# CC2530.net
KiCad netlist of a schematic drawn in Altium Designer
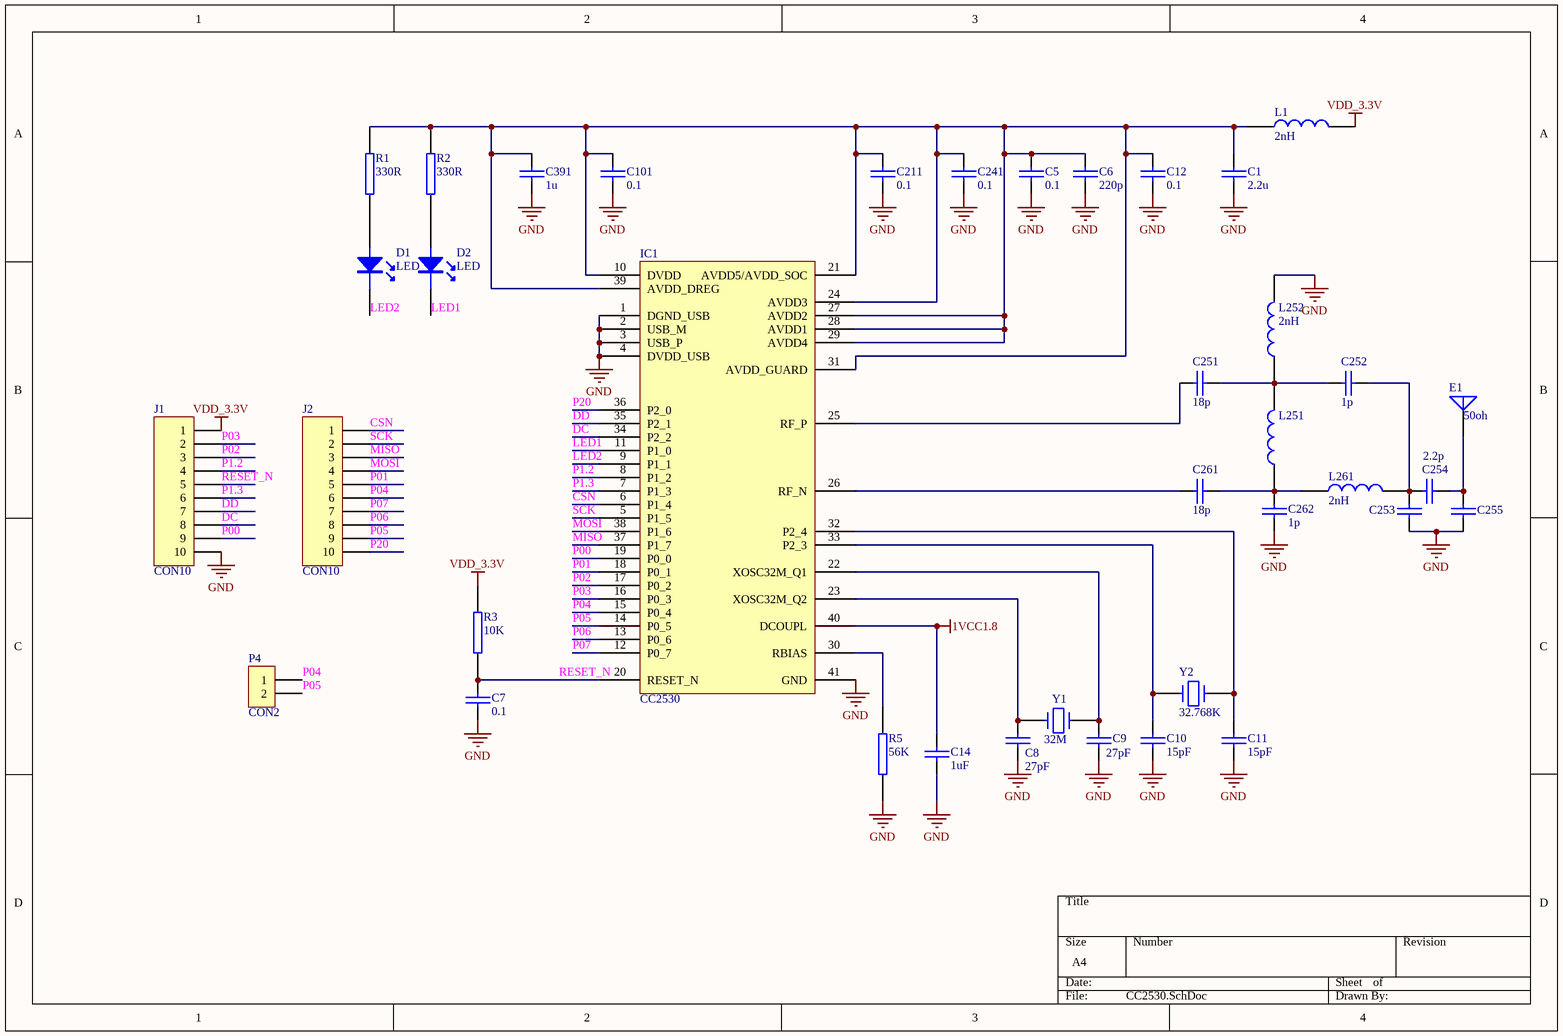
[diagram p0: CC2530.SchDoc]

(export (version "E")
  (design (tool "Eeschema 10.0.6"))
  (components
    (comp (ref "C1")
      (value "2.2u")
      (footprint "0402")
      (description "Capacitor")
      (libsource (lib "Miscellaneous Devices") (part "CAP"))
    )
    (comp (ref "C5")
      (value "0.1")
      (footprint "0402")
      (description "Capacitor")
      (libsource (lib "Miscellaneous Devices") (part "CAP"))
    )
    (comp (ref "C6")
      (value "220p")
      (footprint "0402")
      (description "Capacitor")
      (libsource (lib "Miscellaneous Devices") (part "CAP"))
    )
    (comp (ref "C7")
      (value "0.1")
      (footprint "0402")
      (description "Capacitor")
      (libsource (lib "Miscellaneous Devices") (part "CAP"))
    )
    (comp (ref "C8")
      (value "27pF")
      (footprint "0402")
      (description "Capacitor")
      (libsource (lib "Miscellaneous Devices") (part "CAP"))
    )
    (comp (ref "C9")
      (value "27pF")
      (footprint "0402")
      (description "Capacitor")
      (libsource (lib "Miscellaneous Devices") (part "CAP"))
    )
    (comp (ref "C10")
      (value "15pF")
      (footprint "0402")
      (description "Capacitor")
      (libsource (lib "Miscellaneous Devices") (part "CAP"))
    )
    (comp (ref "C11")
      (value "15pF")
      (footprint "0402")
      (description "Capacitor")
      (libsource (lib "Miscellaneous Devices") (part "CAP"))
    )
    (comp (ref "C12")
      (value "0.1")
      (footprint "0402")
      (description "Capacitor")
      (libsource (lib "Miscellaneous Devices") (part "CAP"))
    )
    (comp (ref "C14")
      (value "1uF")
      (footprint "0402")
      (description "Capacitor")
      (libsource (lib "Miscellaneous Devices") (part "CAP"))
    )
    (comp (ref "C101")
      (value "0.1")
      (footprint "0402")
      (description "Capacitor")
      (libsource (lib "Miscellaneous Devices") (part "CAP"))
    )
    (comp (ref "C211")
      (value "0.1")
      (footprint "0402")
      (description "Capacitor")
      (libsource (lib "Miscellaneous Devices") (part "CAP"))
    )
    (comp (ref "C241")
      (value "0.1")
      (footprint "0402")
      (description "Capacitor")
      (libsource (lib "Miscellaneous Devices") (part "CAP"))
    )
    (comp (ref "C251")
      (value "18p")
      (footprint "0402")
      (description "Capacitor")
      (libsource (lib "Miscellaneous Devices") (part "CAP"))
    )
    (comp (ref "C252")
      (value "1p")
      (footprint "0402")
      (description "Capacitor")
      (libsource (lib "Miscellaneous Devices") (part "CAP"))
    )
    (comp (ref "C253")
      (value "~")
      (footprint "0402")
      (description "Capacitor")
      (libsource (lib "Miscellaneous Devices") (part "CAP"))
    )
    (comp (ref "C254")
      (value "2.2p")
      (footprint "0402")
      (description "Capacitor")
      (libsource (lib "Miscellaneous Devices") (part "CAP"))
    )
    (comp (ref "C255")
      (value "~")
      (footprint "0402")
      (description "Capacitor")
      (libsource (lib "Miscellaneous Devices") (part "CAP"))
    )
    (comp (ref "C261")
      (value "18p")
      (footprint "0402")
      (description "Capacitor")
      (libsource (lib "Miscellaneous Devices") (part "CAP"))
    )
    (comp (ref "C262")
      (value "1p")
      (footprint "0402")
      (description "Capacitor")
      (libsource (lib "Miscellaneous Devices") (part "CAP"))
    )
    (comp (ref "C391")
      (value "1u")
      (footprint "0402")
      (description "Capacitor")
      (libsource (lib "Miscellaneous Devices") (part "CAP"))
    )
    (comp (ref "D1")
      (value "LED")
      (footprint "LED-0603")
      (libsource (lib "Miscellaneous Devices") (part "LED"))
    )
    (comp (ref "D2")
      (value "LED")
      (footprint "LED-0603")
      (libsource (lib "Miscellaneous Devices") (part "LED"))
    )
    (comp (ref "E1")
      (value "50oh")
      (footprint "ANT")
      (description "Generic Antenna")
      (libsource (lib "Miscellaneous Devices") (part "ANTENNA"))
    )
    (comp (ref "IC1") (value "CC2530") (footprint "PVQFN-N40") (libsource (lib "集成") (part "CC2530")))
    (comp (ref "J1")
      (value "CON10")
      (footprint "SIP10-2.0")
      (description "Connector")
      (libsource (lib "Miscellaneous Devices") (part "CON10"))
    )
    (comp (ref "J2")
      (value "CON10")
      (footprint "SIP10-2.0")
      (description "Connector")
      (libsource (lib "Miscellaneous Devices") (part "CON10"))
    )
    (comp (ref "L1")
      (value "2nH")
      (footprint "0402")
      (libsource (lib "Miscellaneous Devices") (part "INDUCTOR"))
    )
    (comp (ref "L251")
      (value "~")
      (footprint "0402")
      (libsource (lib "Miscellaneous Devices") (part "INDUCTOR"))
    )
    (comp (ref "L252")
      (value "2nH")
      (footprint "0402")
      (libsource (lib "Miscellaneous Devices") (part "INDUCTOR"))
    )
    (comp (ref "L261")
      (value "2nH")
      (footprint "0402")
      (libsource (lib "Miscellaneous Devices") (part "INDUCTOR"))
    )
    (comp (ref "P4")
      (value "CON2")
      (footprint "SIP2")
      (description "Connector")
      (libsource (lib "Miscellaneous Devices_99se") (part "CON2"))
    )
    (comp (ref "R1")
      (value "330R")
      (footprint "0402")
      (libsource (lib "Miscellaneous Devices") (part "RES2"))
    )
    (comp (ref "R2")
      (value "330R")
      (footprint "0402")
      (libsource (lib "Miscellaneous Devices") (part "RES2"))
    )
    (comp (ref "R3") (value "10K") (footprint "0402") (libsource (lib "Miscellaneous Devices") (part "RES2")))
    (comp (ref "R5") (value "56K") (footprint "0402") (libsource (lib "Miscellaneous Devices") (part "RES2")))
    (comp (ref "Y1")
      (value "32M")
      (footprint "XT-SMD3225")
      (description "Crystal")
      (libsource (lib "Miscellaneous Devices") (part "CRYSTAL"))
    )
    (comp (ref "Y2")
      (value "32.768K")
      (footprint "XT_3")
      (description "Crystal")
      (libsource (lib "Miscellaneous Devices") (part "CRYSTAL"))
    )
  )
  (nets
    (net (code "1") (name "/CSN") (class "Default")
      (node (ref "IC1") (pin "6") (pinfunction "P1_4_6") (pintype "passive"))
      (node (ref "J2") (pin "1") (pinfunction "1_1") (pintype "passive"))
    )
    (net (code "2") (name "/DC") (class "Default")
      (node (ref "IC1") (pin "34") (pinfunction "P2_2_34") (pintype "passive"))
      (node (ref "J1") (pin "8") (pinfunction "8_8") (pintype "passive"))
    )
    (net (code "3") (name "/DD") (class "Default")
      (node (ref "IC1") (pin "35") (pinfunction "P2_1_35") (pintype "passive"))
      (node (ref "J1") (pin "7") (pinfunction "7_7") (pintype "passive"))
    )
    (net (code "4") (name "/LED1") (class "Default")
      (node (ref "D2") (pin "K") (pinfunction "2_K") (pintype "passive"))
      (node (ref "IC1") (pin "11") (pinfunction "P1_0_11") (pintype "passive"))
    )
    (net (code "5") (name "/LED2") (class "Default")
      (node (ref "D1") (pin "K") (pinfunction "2_K") (pintype "passive"))
      (node (ref "IC1") (pin "9") (pinfunction "P1_1_9") (pintype "passive"))
    )
    (net (code "6") (name "/MISO") (class "Default")
      (node (ref "IC1") (pin "37") (pinfunction "P1_7_37") (pintype "passive"))
      (node (ref "J2") (pin "3") (pinfunction "3_3") (pintype "passive"))
    )
    (net (code "7") (name "/MOSI") (class "Default")
      (node (ref "IC1") (pin "38") (pinfunction "P1_6_38") (pintype "passive"))
      (node (ref "J2") (pin "4") (pinfunction "4_4") (pintype "passive"))
    )
    (net (code "8") (name "/P00") (class "Default")
      (node (ref "IC1") (pin "19") (pinfunction "P0_0_19") (pintype "passive"))
      (node (ref "J1") (pin "9") (pinfunction "9_9") (pintype "passive"))
    )
    (net (code "9") (name "/P01") (class "Default")
      (node (ref "IC1") (pin "18") (pinfunction "P0_1_18") (pintype "passive"))
      (node (ref "J2") (pin "5") (pinfunction "5_5") (pintype "passive"))
    )
    (net (code "10") (name "/P1.2") (class "Default")
      (node (ref "IC1") (pin "8") (pinfunction "P1_2_8") (pintype "passive"))
      (node (ref "J1") (pin "4") (pinfunction "4_4") (pintype "passive"))
    )
    (net (code "11") (name "/P1.3") (class "Default")
      (node (ref "IC1") (pin "7") (pinfunction "P1_3_7") (pintype "passive"))
      (node (ref "J1") (pin "6") (pinfunction "6_6") (pintype "passive"))
    )
    (net (code "12") (name "/P02") (class "Default")
      (node (ref "IC1") (pin "17") (pinfunction "P0_2_17") (pintype "passive"))
      (node (ref "J1") (pin "3") (pinfunction "3_3") (pintype "passive"))
    )
    (net (code "13") (name "/P03") (class "Default")
      (node (ref "IC1") (pin "16") (pinfunction "P0_3_16") (pintype "passive"))
      (node (ref "J1") (pin "2") (pinfunction "2_2") (pintype "passive"))
    )
    (net (code "14") (name "/P04") (class "Default")
      (node (ref "IC1") (pin "15") (pinfunction "P0_4_15") (pintype "passive"))
      (node (ref "J2") (pin "6") (pinfunction "6_6") (pintype "passive"))
      (node (ref "P4") (pin "1") (pinfunction "1_1") (pintype "passive"))
    )
    (net (code "15") (name "/P05") (class "Default")
      (node (ref "IC1") (pin "14") (pinfunction "P0_5_14") (pintype "passive"))
      (node (ref "J2") (pin "9") (pinfunction "9_9") (pintype "passive"))
      (node (ref "P4") (pin "2") (pinfunction "2_2") (pintype "passive"))
    )
    (net (code "16") (name "/P06") (class "Default")
      (node (ref "IC1") (pin "13") (pinfunction "P0_6_13") (pintype "passive"))
      (node (ref "J2") (pin "8") (pinfunction "8_8") (pintype "passive"))
    )
    (net (code "17") (name "/P07") (class "Default")
      (node (ref "IC1") (pin "12") (pinfunction "P0_7_12") (pintype "passive"))
      (node (ref "J2") (pin "7") (pinfunction "7_7") (pintype "passive"))
    )
    (net (code "18") (name "/P20") (class "Default")
      (node (ref "IC1") (pin "36") (pinfunction "P2_0_36") (pintype "passive"))
      (node (ref "J2") (pin "10") (pinfunction "10_10") (pintype "passive"))
    )
    (net (code "19") (name "/RESET_N") (class "Default")
      (node (ref "C7") (pin "1") (pinfunction "1_1") (pintype "passive"))
      (node (ref "IC1") (pin "20") (pinfunction "RESET_N_20") (pintype "passive"))
      (node (ref "J1") (pin "5") (pinfunction "5_5") (pintype "passive"))
      (node (ref "R3") (pin "1") (pinfunction "1_1") (pintype "passive"))
    )
    (net (code "20") (name "/SCK") (class "Default")
      (node (ref "IC1") (pin "5") (pinfunction "P1_5_5") (pintype "passive"))
      (node (ref "J2") (pin "2") (pinfunction "2_2") (pintype "passive"))
    )
    (net (code "21") (name "1VCC1.8") (class "Default")
      (node (ref "C14") (pin "1") (pinfunction "1_1") (pintype "passive"))
      (node (ref "IC1") (pin "40") (pinfunction "DCOUPL_40") (pintype "passive"))
    )
    (net (code "22") (name "GND") (class "Default")
      (node (ref "C1") (pin "2") (pinfunction "2_2") (pintype "passive"))
      (node (ref "C10") (pin "2") (pinfunction "2_2") (pintype "passive"))
      (node (ref "C101") (pin "2") (pinfunction "2_2") (pintype "passive"))
      (node (ref "C11") (pin "2") (pinfunction "2_2") (pintype "passive"))
      (node (ref "C12") (pin "2") (pinfunction "2_2") (pintype "passive"))
      (node (ref "C14") (pin "2") (pinfunction "2_2") (pintype "passive"))
      (node (ref "C211") (pin "2") (pinfunction "2_2") (pintype "passive"))
      (node (ref "C241") (pin "2") (pinfunction "2_2") (pintype "passive"))
      (node (ref "C253") (pin "2") (pinfunction "2_2") (pintype "passive"))
      (node (ref "C255") (pin "1") (pinfunction "1_1") (pintype "passive"))
      (node (ref "C262") (pin "2") (pinfunction "2_2") (pintype "passive"))
      (node (ref "C391") (pin "2") (pinfunction "2_2") (pintype "passive"))
      (node (ref "C5") (pin "2") (pinfunction "2_2") (pintype "passive"))
      (node (ref "C6") (pin "2") (pinfunction "2_2") (pintype "passive"))
      (node (ref "C7") (pin "2") (pinfunction "2_2") (pintype "passive"))
      (node (ref "C8") (pin "2") (pinfunction "2_2") (pintype "passive"))
      (node (ref "C9") (pin "2") (pinfunction "2_2") (pintype "passive"))
      (node (ref "IC1") (pin "1") (pinfunction "DGND_USB_1") (pintype "passive"))
      (node (ref "IC1") (pin "2") (pinfunction "USB_M_2") (pintype "passive"))
      (node (ref "IC1") (pin "3") (pinfunction "USB_P_3") (pintype "passive"))
      (node (ref "IC1") (pin "4") (pinfunction "DVDD_USB_4") (pintype "passive"))
      (node (ref "IC1") (pin "41") (pinfunction "GND_41") (pintype "passive"))
      (node (ref "J1") (pin "10") (pinfunction "10_10") (pintype "passive"))
      (node (ref "L252") (pin "2") (pinfunction "2_2") (pintype "passive"))
      (node (ref "R5") (pin "2") (pinfunction "2_2") (pintype "passive"))
    )
    (net (code "23") (name "Net-(C251-Pad2)") (class "Default")
      (node (ref "C251") (pin "2") (pinfunction "2_2") (pintype "passive"))
      (node (ref "C252") (pin "1") (pinfunction "1_1") (pintype "passive"))
      (node (ref "L251") (pin "2") (pinfunction "2_2") (pintype "passive"))
      (node (ref "L252") (pin "1") (pinfunction "1_1") (pintype "passive"))
    )
    (net (code "24") (name "Net-(C252-Pad2)") (class "Default")
      (node (ref "C252") (pin "2") (pinfunction "2_2") (pintype "passive"))
      (node (ref "C253") (pin "1") (pinfunction "1_1") (pintype "passive"))
      (node (ref "C254") (pin "1") (pinfunction "1_1") (pintype "passive"))
      (node (ref "L261") (pin "2") (pinfunction "2_2") (pintype "passive"))
    )
    (net (code "25") (name "Net-(C261-Pad2)") (class "Default")
      (node (ref "C261") (pin "2") (pinfunction "2_2") (pintype "passive"))
      (node (ref "C262") (pin "1") (pinfunction "1_1") (pintype "passive"))
      (node (ref "L251") (pin "1") (pinfunction "1_1") (pintype "passive"))
      (node (ref "L261") (pin "1") (pinfunction "1_1") (pintype "passive"))
    )
    (net (code "26") (name "Net-(D1-1)") (class "Default")
      (node (ref "D1") (pin "A") (pinfunction "1_A") (pintype "passive"))
      (node (ref "R1") (pin "1") (pinfunction "1_1") (pintype "passive"))
    )
    (net (code "27") (name "Net-(D2-1)") (class "Default")
      (node (ref "D2") (pin "A") (pinfunction "1_A") (pintype "passive"))
      (node (ref "R2") (pin "1") (pinfunction "1_1") (pintype "passive"))
    )
    (net (code "28") (name "Net-(E1-A)") (class "Default")
      (node (ref "C254") (pin "2") (pinfunction "2_2") (pintype "passive"))
      (node (ref "C255") (pin "2") (pinfunction "2_2") (pintype "passive"))
      (node (ref "E1") (pin "1") (pinfunction "A_1") (pintype "passive"))
    )
    (net (code "29") (name "Net-(IC1-AVDD1)") (class "Default")
      (node (ref "C1") (pin "1") (pinfunction "1_1") (pintype "passive"))
      (node (ref "C101") (pin "1") (pinfunction "1_1") (pintype "passive"))
      (node (ref "C12") (pin "1") (pinfunction "1_1") (pintype "passive"))
      (node (ref "C211") (pin "1") (pinfunction "1_1") (pintype "passive"))
      (node (ref "C241") (pin "1") (pinfunction "1_1") (pintype "passive"))
      (node (ref "C391") (pin "1") (pinfunction "1_1") (pintype "passive"))
      (node (ref "C5") (pin "1") (pinfunction "1_1") (pintype "passive"))
      (node (ref "C6") (pin "1") (pinfunction "1_1") (pintype "passive"))
      (node (ref "IC1") (pin "10") (pinfunction "DVDD_10") (pintype "passive"))
      (node (ref "IC1") (pin "21") (pinfunction "AVDD5/AVDD_SOC_21") (pintype "passive"))
      (node (ref "IC1") (pin "24") (pinfunction "AVDD3_24") (pintype "passive"))
      (node (ref "IC1") (pin "27") (pinfunction "AVDD2_27") (pintype "passive"))
      (node (ref "IC1") (pin "28") (pinfunction "AVDD1_28") (pintype "passive"))
      (node (ref "IC1") (pin "29") (pinfunction "AVDD4_29") (pintype "passive"))
      (node (ref "IC1") (pin "31") (pinfunction "AVDD_GUARD_31") (pintype "passive"))
      (node (ref "IC1") (pin "39") (pinfunction "AVDD_DREG_39") (pintype "passive"))
      (node (ref "L1") (pin "1") (pinfunction "1_1") (pintype "passive"))
      (node (ref "R1") (pin "2") (pinfunction "2_2") (pintype "passive"))
      (node (ref "R2") (pin "2") (pinfunction "2_2") (pintype "passive"))
    )
    (net (code "30") (name "Net-(IC1-P2_3)") (class "Default")
      (node (ref "C10") (pin "1") (pinfunction "1_1") (pintype "passive"))
      (node (ref "IC1") (pin "33") (pinfunction "P2_3_33") (pintype "passive"))
      (node (ref "Y2") (pin "2") (pinfunction "2_2") (pintype "passive"))
    )
    (net (code "31") (name "Net-(IC1-P2_4)") (class "Default")
      (node (ref "C11") (pin "1") (pinfunction "1_1") (pintype "passive"))
      (node (ref "IC1") (pin "32") (pinfunction "P2_4_32") (pintype "passive"))
      (node (ref "Y2") (pin "1") (pinfunction "1_1") (pintype "passive"))
    )
    (net (code "32") (name "Net-(IC1-RBIAS)") (class "Default")
      (node (ref "IC1") (pin "30") (pinfunction "RBIAS_30") (pintype "passive"))
      (node (ref "R5") (pin "1") (pinfunction "1_1") (pintype "passive"))
    )
    (net (code "33") (name "Net-(IC1-RF_N)") (class "Default")
      (node (ref "C261") (pin "1") (pinfunction "1_1") (pintype "passive"))
      (node (ref "IC1") (pin "26") (pinfunction "RF_N_26") (pintype "passive"))
    )
    (net (code "34") (name "Net-(IC1-RF_P)") (class "Default")
      (node (ref "C251") (pin "1") (pinfunction "1_1") (pintype "passive"))
      (node (ref "IC1") (pin "25") (pinfunction "RF_P_25") (pintype "passive"))
    )
    (net (code "35") (name "Net-(IC1-XOSC32M_Q1)") (class "Default")
      (node (ref "C9") (pin "1") (pinfunction "1_1") (pintype "passive"))
      (node (ref "IC1") (pin "22") (pinfunction "XOSC32M_Q1_22") (pintype "passive"))
      (node (ref "Y1") (pin "2") (pinfunction "2_2") (pintype "passive"))
    )
    (net (code "36") (name "Net-(IC1-XOSC32M_Q2)") (class "Default")
      (node (ref "C8") (pin "1") (pinfunction "1_1") (pintype "passive"))
      (node (ref "IC1") (pin "23") (pinfunction "XOSC32M_Q2_23") (pintype "passive"))
      (node (ref "Y1") (pin "1") (pinfunction "1_1") (pintype "passive"))
    )
    (net (code "37") (name "VDD_3.3V") (class "Default")
      (node (ref "J1") (pin "1") (pinfunction "1_1") (pintype "passive"))
      (node (ref "L1") (pin "2") (pinfunction "2_2") (pintype "passive"))
      (node (ref "R3") (pin "2") (pinfunction "2_2") (pintype "passive"))
    )
  )
)
